# AmpliRF.net
KiCad netlist of a schematic drawn in Altium Designer
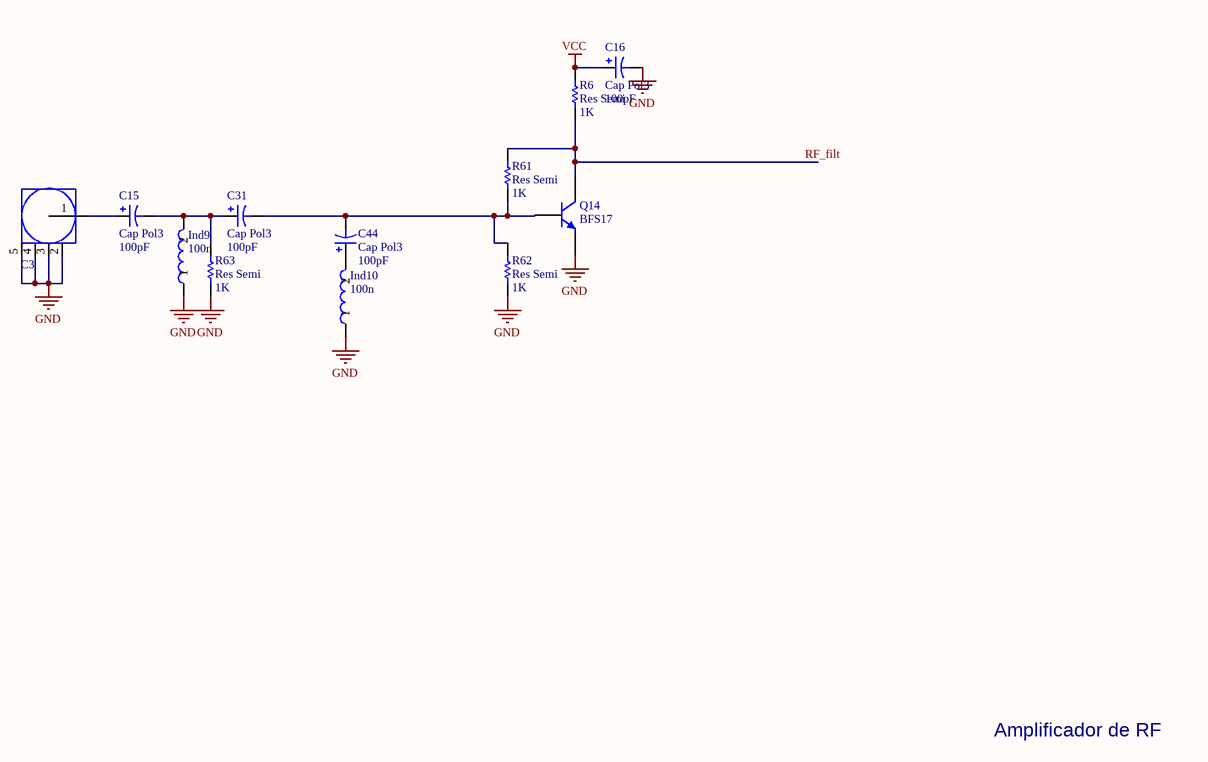
[diagram p0: AmpliRF.SchDoc]

(export (version "E")
  (design (tool "Eeschema 10.0.6"))
  (components
    (comp (ref "C3") (value "SMA") (footprint "SMA1") (libsource (lib "epf") (part "SMA")))
    (comp (ref "C15")
      (value "Cap Pol3")
      (footprint "C0805")
      (description "Polarized Capacitor (Surface Mount)")
      (fields (field (name "ALTIUM_VALUE") "100pF") (field (name "PUBLISHER") "Altium Limited"))
      (libsource (lib "Miscellaneous Devices") (part "Cap Pol3"))
    )
    (comp (ref "C16")
      (value "Cap Pol3")
      (footprint "C0805")
      (description "Polarized Capacitor (Surface Mount)")
      (fields (field (name "ALTIUM_VALUE") "100pF") (field (name "PUBLISHER") "Altium Limited"))
      (libsource (lib "Miscellaneous Devices") (part "Cap Pol3"))
    )
    (comp (ref "C31")
      (value "Cap Pol3")
      (footprint "C0805")
      (description "Polarized Capacitor (Surface Mount)")
      (fields (field (name "ALTIUM_VALUE") "100pF") (field (name "PUBLISHER") "Altium Limited"))
      (libsource (lib "Miscellaneous Devices") (part "Cap Pol3"))
    )
    (comp (ref "C44")
      (value "Cap Pol3")
      (footprint "C0805")
      (description "Polarized Capacitor (Surface Mount)")
      (fields (field (name "ALTIUM_VALUE") "100pF") (field (name "PUBLISHER") "Altium Limited"))
      (libsource (lib "Miscellaneous Devices") (part "Cap Pol3"))
    )
    (comp (ref "Ind9")
      (value "Ind2")
      (footprint "Ind_4mm")
      (fields (field (name "VALOR") "100n"))
      (libsource (lib "epf") (part "Ind2"))
    )
    (comp (ref "Ind10")
      (value "Ind2")
      (footprint "Ind_4mm")
      (fields (field (name "VALOR") "100n"))
      (libsource (lib "epf") (part "Ind2"))
    )
    (comp (ref "Q14")
      (value "BFS17")
      (footprint "SOT-23")
      (description "NPN 1 GHz Wideband Transistor")
      (fields (field (name "PUBLISHER") "Altium Limited"))
      (libsource (lib "Philips Discrete BJT - RF Transistor") (part "BFS17"))
    )
    (comp (ref "R6")
      (value "Res Semi")
      (footprint "2012[0805]")
      (description "Semiconductor Resistor")
      (fields (field (name "ALTIUM_VALUE") "1K") (field (name "PUBLISHER") "Altium Limited"))
      (libsource (lib "Miscellaneous Devices") (part "Res Semi"))
    )
    (comp (ref "R61")
      (value "Res Semi")
      (footprint "2012[0805]")
      (description "Semiconductor Resistor")
      (fields (field (name "ALTIUM_VALUE") "1K") (field (name "PUBLISHER") "Altium Limited"))
      (libsource (lib "Miscellaneous Devices") (part "Res Semi"))
    )
    (comp (ref "R62")
      (value "Res Semi")
      (footprint "2012[0805]")
      (description "Semiconductor Resistor")
      (fields (field (name "ALTIUM_VALUE") "1K") (field (name "PUBLISHER") "Altium Limited"))
      (libsource (lib "Miscellaneous Devices") (part "Res Semi"))
    )
    (comp (ref "R63")
      (value "Res Semi")
      (footprint "2012[0805]")
      (description "Semiconductor Resistor")
      (fields (field (name "ALTIUM_VALUE") "1K") (field (name "PUBLISHER") "Altium Limited"))
      (libsource (lib "Miscellaneous Devices") (part "Res Semi"))
    )
  )
  (nets
    (net (code "1") (name "/RF_filt") (class "Default")
      (node (ref "Q14") (pin "3") (pinfunction "C_3") (pintype "passive"))
      (node (ref "R6") (pin "2") (pinfunction "2_2") (pintype "passive"))
      (node (ref "R61") (pin "1") (pinfunction "1_1") (pintype "passive"))
    )
    (net (code "2") (name "GND") (class "Default")
      (node (ref "C16") (pin "2") (pinfunction "2_2") (pintype "passive"))
      (node (ref "C3") (pin "2") (pinfunction "GND_2") (pintype "passive"))
      (node (ref "C3") (pin "3") (pinfunction "GND_3") (pintype "passive"))
      (node (ref "C3") (pin "4") (pinfunction "GND_4") (pintype "passive"))
      (node (ref "C3") (pin "5") (pinfunction "GND_5") (pintype "passive"))
      (node (ref "Ind10") (pin "1") (pinfunction "1_1") (pintype "passive"))
      (node (ref "Ind9") (pin "1") (pinfunction "1_1") (pintype "passive"))
      (node (ref "Q14") (pin "2") (pinfunction "E_2") (pintype "passive"))
      (node (ref "R62") (pin "2") (pinfunction "2_2") (pintype "passive"))
      (node (ref "R63") (pin "2") (pinfunction "2_2") (pintype "passive"))
    )
    (net (code "3") (name "Net-(C3-RF)") (class "Default")
      (node (ref "C15") (pin "1") (pinfunction "1_1") (pintype "passive"))
      (node (ref "C3") (pin "1") (pinfunction "RF_1") (pintype "passive"))
    )
    (net (code "4") (name "Net-(C15-Pad2)") (class "Default")
      (node (ref "C15") (pin "2") (pinfunction "2_2") (pintype "passive"))
      (node (ref "C31") (pin "1") (pinfunction "1_1") (pintype "passive"))
      (node (ref "Ind9") (pin "2") (pinfunction "2_2") (pintype "passive"))
      (node (ref "R63") (pin "1") (pinfunction "1_1") (pintype "passive"))
    )
    (net (code "5") (name "Net-(C44-Pad1)") (class "Default")
      (node (ref "C44") (pin "1") (pinfunction "1_1") (pintype "passive"))
      (node (ref "Ind10") (pin "2") (pinfunction "2_2") (pintype "passive"))
    )
    (net (code "6") (name "Net-(Q14-B)") (class "Default")
      (node (ref "C31") (pin "2") (pinfunction "2_2") (pintype "passive"))
      (node (ref "C44") (pin "2") (pinfunction "2_2") (pintype "passive"))
      (node (ref "Q14") (pin "1") (pinfunction "B_1") (pintype "passive"))
      (node (ref "R61") (pin "2") (pinfunction "2_2") (pintype "passive"))
      (node (ref "R62") (pin "1") (pinfunction "1_1") (pintype "passive"))
    )
    (net (code "7") (name "VCC") (class "Default")
      (node (ref "C16") (pin "1") (pinfunction "1_1") (pintype "passive"))
      (node (ref "R6") (pin "1") (pinfunction "1_1") (pintype "passive"))
    )
  )
)
